# VGA_DAC.net
KiCad netlist of a schematic drawn in Altium Designer
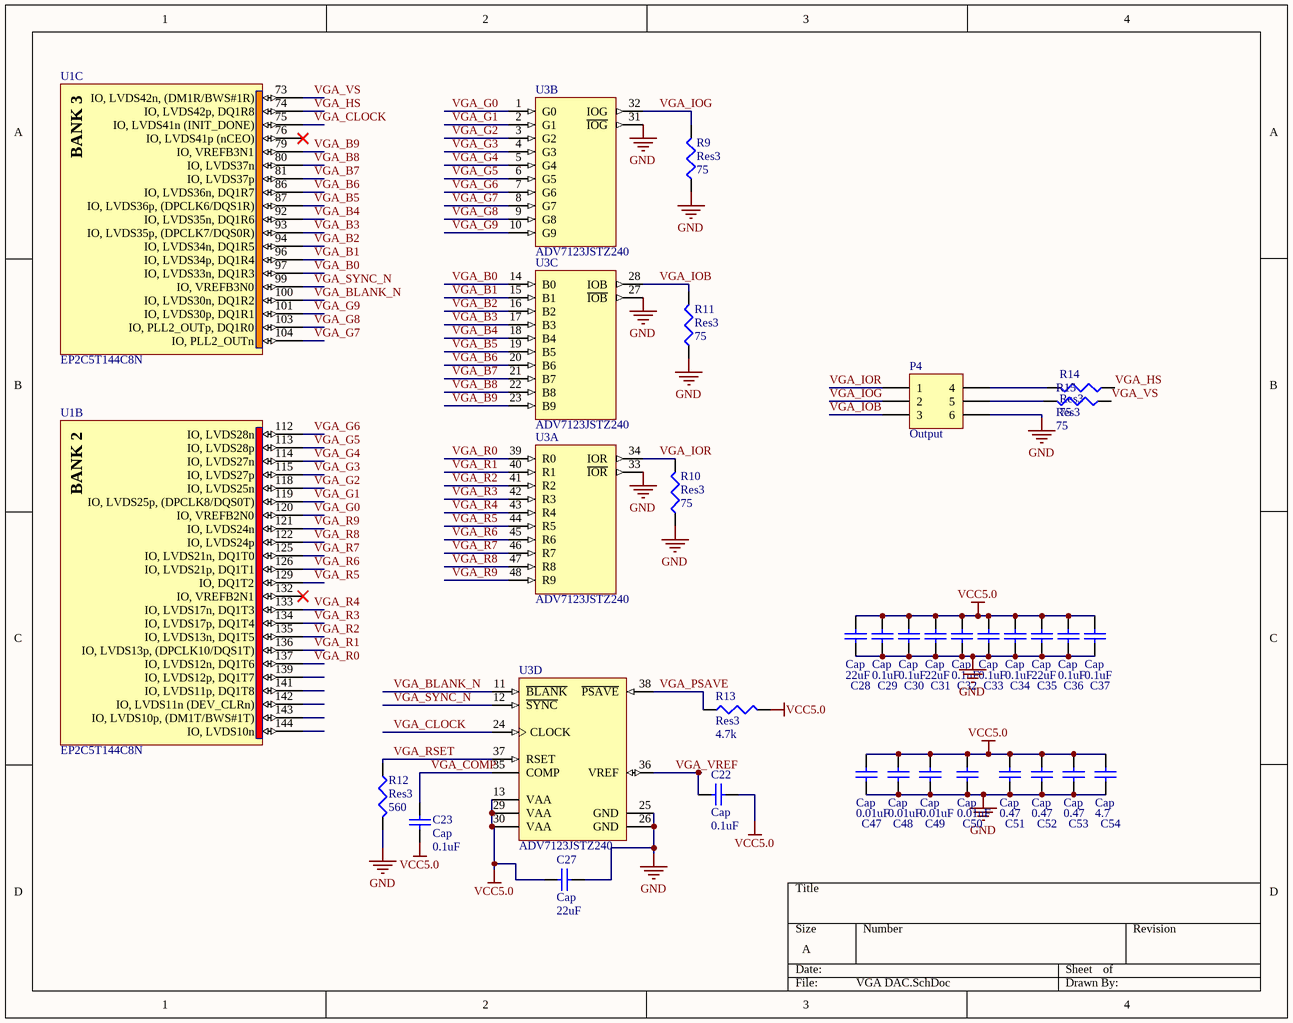
[diagram p0: VGA DAC.SchDoc]

(export (version "E")
  (design (tool "Eeschema 10.0.6"))
  (components
    (comp (ref "C22")
      (value "Cap")
      (footprint "1608[0603]")
      (description "Capacitor (Semiconductor SIM Model)")
      (fields (field (name "ALTIUM_VALUE") "0.1uF") (field (name "PUBLISHER") "Altium Limited"))
      (libsource (lib "Miscellaneous Devices") (part "Cap Semi"))
    )
    (comp (ref "C23")
      (value "Cap")
      (footprint "1608[0603]")
      (description "Capacitor (Semiconductor SIM Model)")
      (fields (field (name "ALTIUM_VALUE") "0.1uF") (field (name "PUBLISHER") "Altium Limited"))
      (libsource (lib "Miscellaneous Devices") (part "Cap Semi"))
    )
    (comp (ref "C27")
      (value "Cap")
      (footprint "1608[0603]")
      (description "Capacitor (Semiconductor SIM Model)")
      (fields (field (name "ALTIUM_VALUE") "22uF") (field (name "PUBLISHER") "Altium Limited"))
      (libsource (lib "Miscellaneous Devices") (part "Cap Semi"))
    )
    (comp (ref "C28")
      (value "Cap")
      (footprint "1608[0603]")
      (description "Capacitor (Semiconductor SIM Model)")
      (fields (field (name "ALTIUM_VALUE") "22uF") (field (name "PUBLISHER") "Altium Limited"))
      (libsource (lib "Miscellaneous Devices") (part "Cap Semi"))
    )
    (comp (ref "C29")
      (value "Cap")
      (footprint "1608[0603]")
      (description "Capacitor (Semiconductor SIM Model)")
      (fields (field (name "ALTIUM_VALUE") "0.1uF") (field (name "PUBLISHER") "Altium Limited"))
      (libsource (lib "Miscellaneous Devices") (part "Cap Semi"))
    )
    (comp (ref "C30")
      (value "Cap")
      (footprint "1608[0603]")
      (description "Capacitor (Semiconductor SIM Model)")
      (fields (field (name "ALTIUM_VALUE") "0.1uF") (field (name "PUBLISHER") "Altium Limited"))
      (libsource (lib "Miscellaneous Devices") (part "Cap Semi"))
    )
    (comp (ref "C31")
      (value "Cap")
      (footprint "1608[0603]")
      (description "Capacitor (Semiconductor SIM Model)")
      (fields (field (name "ALTIUM_VALUE") "22uF") (field (name "PUBLISHER") "Altium Limited"))
      (libsource (lib "Miscellaneous Devices") (part "Cap Semi"))
    )
    (comp (ref "C32")
      (value "Cap")
      (footprint "1608[0603]")
      (description "Capacitor (Semiconductor SIM Model)")
      (fields (field (name "ALTIUM_VALUE") "0.1uF") (field (name "PUBLISHER") "Altium Limited"))
      (libsource (lib "Miscellaneous Devices") (part "Cap Semi"))
    )
    (comp (ref "C33")
      (value "Cap")
      (footprint "1608[0603]")
      (description "Capacitor (Semiconductor SIM Model)")
      (fields (field (name "ALTIUM_VALUE") "0.1uF") (field (name "PUBLISHER") "Altium Limited"))
      (libsource (lib "Miscellaneous Devices") (part "Cap Semi"))
    )
    (comp (ref "C34")
      (value "Cap")
      (footprint "1608[0603]")
      (description "Capacitor (Semiconductor SIM Model)")
      (fields (field (name "ALTIUM_VALUE") "0.1uF") (field (name "PUBLISHER") "Altium Limited"))
      (libsource (lib "Miscellaneous Devices") (part "Cap Semi"))
    )
    (comp (ref "C35")
      (value "Cap")
      (footprint "1608[0603]")
      (description "Capacitor (Semiconductor SIM Model)")
      (fields (field (name "ALTIUM_VALUE") "22uF") (field (name "PUBLISHER") "Altium Limited"))
      (libsource (lib "Miscellaneous Devices") (part "Cap Semi"))
    )
    (comp (ref "C36")
      (value "Cap")
      (footprint "1608[0603]")
      (description "Capacitor (Semiconductor SIM Model)")
      (fields (field (name "ALTIUM_VALUE") "0.1uF") (field (name "PUBLISHER") "Altium Limited"))
      (libsource (lib "Miscellaneous Devices") (part "Cap Semi"))
    )
    (comp (ref "C37")
      (value "Cap")
      (footprint "1608[0603]")
      (description "Capacitor (Semiconductor SIM Model)")
      (fields (field (name "ALTIUM_VALUE") "0.1uF") (field (name "PUBLISHER") "Altium Limited"))
      (libsource (lib "Miscellaneous Devices") (part "Cap Semi"))
    )
    (comp (ref "C47")
      (value "Cap")
      (footprint "1608[0603]")
      (description "Capacitor (Semiconductor SIM Model)")
      (fields (field (name "ALTIUM_VALUE") "0.01uF") (field (name "PUBLISHER") "Altium Limited"))
      (libsource (lib "Miscellaneous Devices") (part "Cap Semi"))
    )
    (comp (ref "C48")
      (value "Cap")
      (footprint "1608[0603]")
      (description "Capacitor (Semiconductor SIM Model)")
      (fields (field (name "ALTIUM_VALUE") "0.01uF") (field (name "PUBLISHER") "Altium Limited"))
      (libsource (lib "Miscellaneous Devices") (part "Cap Semi"))
    )
    (comp (ref "C49")
      (value "Cap")
      (footprint "1608[0603]")
      (description "Capacitor (Semiconductor SIM Model)")
      (fields (field (name "ALTIUM_VALUE") "0.01uF") (field (name "PUBLISHER") "Altium Limited"))
      (libsource (lib "Miscellaneous Devices") (part "Cap Semi"))
    )
    (comp (ref "C50")
      (value "Cap")
      (footprint "1608[0603]")
      (description "Capacitor (Semiconductor SIM Model)")
      (fields (field (name "ALTIUM_VALUE") "0.01uF") (field (name "PUBLISHER") "Altium Limited"))
      (libsource (lib "Miscellaneous Devices") (part "Cap Semi"))
    )
    (comp (ref "C51")
      (value "Cap")
      (footprint "1608[0603]")
      (description "Capacitor (Semiconductor SIM Model)")
      (fields (field (name "ALTIUM_VALUE") "0.47") (field (name "PUBLISHER") "Altium Limited"))
      (libsource (lib "Miscellaneous Devices") (part "Cap Semi"))
    )
    (comp (ref "C52")
      (value "Cap")
      (footprint "1608[0603]")
      (description "Capacitor (Semiconductor SIM Model)")
      (fields (field (name "ALTIUM_VALUE") "0.47") (field (name "PUBLISHER") "Altium Limited"))
      (libsource (lib "Miscellaneous Devices") (part "Cap Semi"))
    )
    (comp (ref "C53")
      (value "Cap")
      (footprint "1608[0603]")
      (description "Capacitor (Semiconductor SIM Model)")
      (fields (field (name "ALTIUM_VALUE") "0.47") (field (name "PUBLISHER") "Altium Limited"))
      (libsource (lib "Miscellaneous Devices") (part "Cap Semi"))
    )
    (comp (ref "C54")
      (value "Cap")
      (footprint "1608[0603]")
      (description "Capacitor (Semiconductor SIM Model)")
      (fields (field (name "ALTIUM_VALUE") "4.7") (field (name "PUBLISHER") "Altium Limited"))
      (libsource (lib "Miscellaneous Devices") (part "Cap Semi"))
    )
    (comp (ref "P4")
      (value "Output")
      (footprint "HDR2X3_CEN")
      (description "Header, 3-Pin, Dual row")
      (fields (field (name "PUBLISHER") "Altium Limited"))
      (libsource (lib "Miscellaneous Connectors") (part "Header 3X2A"))
    )
    (comp (ref "R9")
      (value "Res3")
      (footprint "J1-0603")
      (description "Resistor")
      (fields (field (name "ALTIUM_VALUE") "75") (field (name "PUBLISHER") "Altium Limited"))
      (libsource (lib "Miscellaneous Devices") (part "Res3"))
    )
    (comp (ref "R10")
      (value "Res3")
      (footprint "J1-0603")
      (description "Resistor")
      (fields (field (name "ALTIUM_VALUE") "75") (field (name "PUBLISHER") "Altium Limited"))
      (libsource (lib "Miscellaneous Devices") (part "Res3"))
    )
    (comp (ref "R11")
      (value "Res3")
      (footprint "J1-0603")
      (description "Resistor")
      (fields (field (name "ALTIUM_VALUE") "75") (field (name "PUBLISHER") "Altium Limited"))
      (libsource (lib "Miscellaneous Devices") (part "Res3"))
    )
    (comp (ref "R12")
      (value "Res3")
      (footprint "J1-0603")
      (description "Resistor")
      (fields (field (name "ALTIUM_VALUE") "560") (field (name "PUBLISHER") "Altium Limited"))
      (libsource (lib "Miscellaneous Devices") (part "Res3"))
    )
    (comp (ref "R13")
      (value "Res3")
      (footprint "J1-0603")
      (description "Resistor")
      (fields (field (name "ALTIUM_VALUE") "4.7k") (field (name "PUBLISHER") "Altium Limited"))
      (libsource (lib "Miscellaneous Devices") (part "Res3"))
    )
    (comp (ref "R14")
      (value "Res3")
      (footprint "J1-0603")
      (description "Resistor")
      (fields (field (name "ALTIUM_VALUE") "75") (field (name "PUBLISHER") "Altium Limited"))
      (libsource (lib "Miscellaneous Devices") (part "Res3"))
    )
    (comp (ref "R15")
      (value "Res3")
      (footprint "J1-0603")
      (description "Resistor")
      (fields (field (name "ALTIUM_VALUE") "75") (field (name "PUBLISHER") "Altium Limited"))
      (libsource (lib "Miscellaneous Devices") (part "Res3"))
    )
    (comp (ref "U1")
      (value "EP2C5T144C8N")
      (footprint "TQFP144_N")
      (fields (field (name "PUBLISHER") "Altium Limited"))
      (libsource (lib "Altera Cyclone II") (part "EP2C5T144C8N"))
    )
    (comp (ref "U3")
      (value "ADV7123JSTZ240")
      (footprint "ST-48_N")
      (fields (field (name "GENERIC PART NUMBER") "ADV7123") (field (name "MANUFACTURER") "Analog Devices"))
      (libsource (lib "Analog Devices Data Converters Digital-to-Analog Converters") (part "ADV7123JSTZ240"))
    )
  )
  (nets
    (net (code "1") (name "/VGA_B0") (class "Default")
      (node (ref "U1") (pin "97") (pinfunction "IO,_LVDS33n,_DQ1R3_97") (pintype "bidirectional"))
      (node (ref "U3") (pin "14") (pinfunction "B0_14") (pintype "input"))
    )
    (net (code "2") (name "/VGA_B1") (class "Default")
      (node (ref "U1") (pin "96") (pinfunction "IO,_LVDS34p,_DQ1R4_96") (pintype "bidirectional"))
      (node (ref "U3") (pin "15") (pinfunction "B1_15") (pintype "input"))
    )
    (net (code "3") (name "/VGA_B2") (class "Default")
      (node (ref "U1") (pin "94") (pinfunction "IO,_LVDS34n,_DQ1R5_94") (pintype "bidirectional"))
      (node (ref "U3") (pin "16") (pinfunction "B2_16") (pintype "input"))
    )
    (net (code "4") (name "/VGA_B3") (class "Default")
      (node (ref "U1") (pin "93") (pinfunction "IO,_LVDS35p,_(DPCLK7/DQS0R)_93") (pintype "bidirectional"))
      (node (ref "U3") (pin "17") (pinfunction "B3_17") (pintype "input"))
    )
    (net (code "5") (name "/VGA_B4") (class "Default")
      (node (ref "U1") (pin "92") (pinfunction "IO,_LVDS35n,_DQ1R6_92") (pintype "bidirectional"))
      (node (ref "U3") (pin "18") (pinfunction "B4_18") (pintype "input"))
    )
    (net (code "6") (name "/VGA_B5") (class "Default")
      (node (ref "U1") (pin "87") (pinfunction "IO,_LVDS36p,_(DPCLK6/DQS1R)_87") (pintype "bidirectional"))
      (node (ref "U3") (pin "19") (pinfunction "B5_19") (pintype "input"))
    )
    (net (code "7") (name "/VGA_B6") (class "Default")
      (node (ref "U1") (pin "86") (pinfunction "IO,_LVDS36n,_DQ1R7_86") (pintype "bidirectional"))
      (node (ref "U3") (pin "20") (pinfunction "B6_20") (pintype "input"))
    )
    (net (code "8") (name "/VGA_B7") (class "Default")
      (node (ref "U1") (pin "81") (pinfunction "IO,_LVDS37p_81") (pintype "bidirectional"))
      (node (ref "U3") (pin "21") (pinfunction "B7_21") (pintype "input"))
    )
    (net (code "9") (name "/VGA_B8") (class "Default")
      (node (ref "U1") (pin "80") (pinfunction "IO,_LVDS37n_80") (pintype "bidirectional"))
      (node (ref "U3") (pin "22") (pinfunction "B8_22") (pintype "input"))
    )
    (net (code "10") (name "/VGA_B9") (class "Default")
      (node (ref "U1") (pin "79") (pinfunction "IO,_VREFB3N1_79") (pintype "bidirectional"))
      (node (ref "U3") (pin "23") (pinfunction "B9_23") (pintype "input"))
    )
    (net (code "11") (name "/VGA_BLANK_N") (class "Default")
      (node (ref "U1") (pin "100") (pinfunction "IO,_LVDS30n,_DQ1R2_100") (pintype "bidirectional"))
      (node (ref "U3") (pin "11") (pinfunction "~{BLANK}_11") (pintype "input"))
    )
    (net (code "12") (name "/VGA_CLOCK") (class "Default")
      (node (ref "U1") (pin "75") (pinfunction "IO,_LVDS41n_(INIT_DONE)_75") (pintype "bidirectional"))
      (node (ref "U3") (pin "24") (pinfunction "CLOCK_24") (pintype "input"))
    )
    (net (code "13") (name "/VGA_COMP") (class "Default")
      (node (ref "C23") (pin "1") (pinfunction "1_1") (pintype "passive"))
      (node (ref "U3") (pin "35") (pinfunction "COMP_35") (pintype "passive"))
    )
    (net (code "14") (name "/VGA_G0") (class "Default")
      (node (ref "U1") (pin "120") (pinfunction "IO,_VREFB2N0_120") (pintype "bidirectional"))
      (node (ref "U3") (pin "1") (pinfunction "G0_1") (pintype "input"))
    )
    (net (code "15") (name "/VGA_G1") (class "Default")
      (node (ref "U1") (pin "119") (pinfunction "IO,_LVDS25p,_(DPCLK8/DQS0T)_119") (pintype "bidirectional"))
      (node (ref "U3") (pin "2") (pinfunction "G1_2") (pintype "input"))
    )
    (net (code "16") (name "/VGA_G2") (class "Default")
      (node (ref "U1") (pin "118") (pinfunction "IO,_LVDS25n_118") (pintype "bidirectional"))
      (node (ref "U3") (pin "3") (pinfunction "G2_3") (pintype "input"))
    )
    (net (code "17") (name "/VGA_G3") (class "Default")
      (node (ref "U1") (pin "115") (pinfunction "IO,_LVDS27p_115") (pintype "bidirectional"))
      (node (ref "U3") (pin "4") (pinfunction "G3_4") (pintype "input"))
    )
    (net (code "18") (name "/VGA_G4") (class "Default")
      (node (ref "U1") (pin "114") (pinfunction "IO,_LVDS27n_114") (pintype "bidirectional"))
      (node (ref "U3") (pin "5") (pinfunction "G4_5") (pintype "input"))
    )
    (net (code "19") (name "/VGA_G5") (class "Default")
      (node (ref "U1") (pin "113") (pinfunction "IO,_LVDS28p_113") (pintype "bidirectional"))
      (node (ref "U3") (pin "6") (pinfunction "G5_6") (pintype "input"))
    )
    (net (code "20") (name "/VGA_G6") (class "Default")
      (node (ref "U1") (pin "112") (pinfunction "IO,_LVDS28n_112") (pintype "bidirectional"))
      (node (ref "U3") (pin "7") (pinfunction "G6_7") (pintype "input"))
    )
    (net (code "21") (name "/VGA_G7") (class "Default")
      (node (ref "U1") (pin "104") (pinfunction "IO,_PLL2_OUTn_104") (pintype "bidirectional"))
      (node (ref "U3") (pin "8") (pinfunction "G7_8") (pintype "input"))
    )
    (net (code "22") (name "/VGA_G8") (class "Default")
      (node (ref "U1") (pin "103") (pinfunction "IO,_PLL2_OUTp,_DQ1R0_103") (pintype "bidirectional"))
      (node (ref "U3") (pin "9") (pinfunction "G8_9") (pintype "input"))
    )
    (net (code "23") (name "/VGA_G9") (class "Default")
      (node (ref "U1") (pin "101") (pinfunction "IO,_LVDS30p,_DQ1R1_101") (pintype "bidirectional"))
      (node (ref "U3") (pin "10") (pinfunction "G9_10") (pintype "input"))
    )
    (net (code "24") (name "/VGA_HS") (class "Default")
      (node (ref "R14") (pin "1") (pinfunction "1_1") (pintype "passive"))
      (node (ref "U1") (pin "74") (pinfunction "IO,_LVDS42p,_DQ1R8_74") (pintype "bidirectional"))
    )
    (net (code "25") (name "/VGA_IOB") (class "Default")
      (node (ref "P4") (pin "3") (pinfunction "3_3") (pintype "passive"))
      (node (ref "R11") (pin "2") (pinfunction "2_2") (pintype "passive"))
      (node (ref "U3") (pin "28") (pinfunction "IOB_28") (pintype "output"))
    )
    (net (code "26") (name "/VGA_IOG") (class "Default")
      (node (ref "P4") (pin "2") (pinfunction "2_2") (pintype "passive"))
      (node (ref "R9") (pin "2") (pinfunction "2_2") (pintype "passive"))
      (node (ref "U3") (pin "32") (pinfunction "IOG_32") (pintype "output"))
    )
    (net (code "27") (name "/VGA_IOR") (class "Default")
      (node (ref "P4") (pin "1") (pinfunction "1_1") (pintype "passive"))
      (node (ref "R10") (pin "2") (pinfunction "2_2") (pintype "passive"))
      (node (ref "U3") (pin "34") (pinfunction "IOR_34") (pintype "output"))
    )
    (net (code "28") (name "/VGA_PSAVE") (class "Default")
      (node (ref "R13") (pin "1") (pinfunction "1_1") (pintype "passive"))
      (node (ref "U3") (pin "38") (pinfunction "~{PSAVE}_38") (pintype "input"))
    )
    (net (code "29") (name "/VGA_R0") (class "Default")
      (node (ref "U1") (pin "137") (pinfunction "IO,_LVDS12n,_DQ1T6_137") (pintype "bidirectional"))
      (node (ref "U3") (pin "39") (pinfunction "R0_39") (pintype "input"))
    )
    (net (code "30") (name "/VGA_R1") (class "Default")
      (node (ref "U1") (pin "136") (pinfunction "IO,_LVDS13p,_(DPCLK10/DQS1T)_136") (pintype "bidirectional"))
      (node (ref "U3") (pin "40") (pinfunction "R1_40") (pintype "input"))
    )
    (net (code "31") (name "/VGA_R2") (class "Default")
      (node (ref "U1") (pin "135") (pinfunction "IO,_LVDS13n,_DQ1T5_135") (pintype "bidirectional"))
      (node (ref "U3") (pin "41") (pinfunction "R2_41") (pintype "input"))
    )
    (net (code "32") (name "/VGA_R3") (class "Default")
      (node (ref "U1") (pin "134") (pinfunction "IO,_LVDS17p,_DQ1T4_134") (pintype "bidirectional"))
      (node (ref "U3") (pin "42") (pinfunction "R3_42") (pintype "input"))
    )
    (net (code "33") (name "/VGA_R4") (class "Default")
      (node (ref "U1") (pin "133") (pinfunction "IO,_LVDS17n,_DQ1T3_133") (pintype "bidirectional"))
      (node (ref "U3") (pin "43") (pinfunction "R4_43") (pintype "input"))
    )
    (net (code "34") (name "/VGA_R5") (class "Default")
      (node (ref "U1") (pin "129") (pinfunction "IO,_DQ1T2_129") (pintype "bidirectional"))
      (node (ref "U3") (pin "44") (pinfunction "R5_44") (pintype "input"))
    )
    (net (code "35") (name "/VGA_R6") (class "Default")
      (node (ref "U1") (pin "126") (pinfunction "IO,_LVDS21p,_DQ1T1_126") (pintype "bidirectional"))
      (node (ref "U3") (pin "45") (pinfunction "R6_45") (pintype "input"))
    )
    (net (code "36") (name "/VGA_R7") (class "Default")
      (node (ref "U1") (pin "125") (pinfunction "IO,_LVDS21n,_DQ1T0_125") (pintype "bidirectional"))
      (node (ref "U3") (pin "46") (pinfunction "R7_46") (pintype "input"))
    )
    (net (code "37") (name "/VGA_R8") (class "Default")
      (node (ref "U1") (pin "122") (pinfunction "IO,_LVDS24p_122") (pintype "bidirectional"))
      (node (ref "U3") (pin "47") (pinfunction "R8_47") (pintype "input"))
    )
    (net (code "38") (name "/VGA_R9") (class "Default")
      (node (ref "U1") (pin "121") (pinfunction "IO,_LVDS24n_121") (pintype "bidirectional"))
      (node (ref "U3") (pin "48") (pinfunction "R9_48") (pintype "input"))
    )
    (net (code "39") (name "/VGA_RSET") (class "Default")
      (node (ref "R12") (pin "1") (pinfunction "1_1") (pintype "passive"))
      (node (ref "U3") (pin "37") (pinfunction "RSET_37") (pintype "input"))
    )
    (net (code "40") (name "/VGA_SYNC_N") (class "Default")
      (node (ref "U1") (pin "99") (pinfunction "IO,_VREFB3N0_99") (pintype "bidirectional"))
      (node (ref "U3") (pin "12") (pinfunction "~{SYNC}_12") (pintype "input"))
    )
    (net (code "41") (name "/VGA_VREF") (class "Default")
      (node (ref "C22") (pin "2") (pinfunction "2_2") (pintype "passive"))
      (node (ref "U3") (pin "36") (pinfunction "VREF_36") (pintype "bidirectional"))
    )
    (net (code "42") (name "/VGA_VS") (class "Default")
      (node (ref "R15") (pin "1") (pinfunction "1_1") (pintype "passive"))
      (node (ref "U1") (pin "73") (pinfunction "IO,_LVDS42n,_(DM1R/BWS#1R)_73") (pintype "bidirectional"))
    )
    (net (code "43") (name "GND") (class "Default")
      (node (ref "C27") (pin "1") (pinfunction "1_1") (pintype "passive"))
      (node (ref "C28") (pin "2") (pinfunction "2_2") (pintype "passive"))
      (node (ref "C29") (pin "2") (pinfunction "2_2") (pintype "passive"))
      (node (ref "C30") (pin "2") (pinfunction "2_2") (pintype "passive"))
      (node (ref "C31") (pin "2") (pinfunction "2_2") (pintype "passive"))
      (node (ref "C32") (pin "2") (pinfunction "2_2") (pintype "passive"))
      (node (ref "C33") (pin "2") (pinfunction "2_2") (pintype "passive"))
      (node (ref "C34") (pin "2") (pinfunction "2_2") (pintype "passive"))
      (node (ref "C35") (pin "2") (pinfunction "2_2") (pintype "passive"))
      (node (ref "C36") (pin "2") (pinfunction "2_2") (pintype "passive"))
      (node (ref "C37") (pin "2") (pinfunction "2_2") (pintype "passive"))
      (node (ref "C47") (pin "2") (pinfunction "2_2") (pintype "passive"))
      (node (ref "C48") (pin "2") (pinfunction "2_2") (pintype "passive"))
      (node (ref "C49") (pin "2") (pinfunction "2_2") (pintype "passive"))
      (node (ref "C50") (pin "2") (pinfunction "2_2") (pintype "passive"))
      (node (ref "C51") (pin "2") (pinfunction "2_2") (pintype "passive"))
      (node (ref "C52") (pin "2") (pinfunction "2_2") (pintype "passive"))
      (node (ref "C53") (pin "2") (pinfunction "2_2") (pintype "passive"))
      (node (ref "C54") (pin "2") (pinfunction "2_2") (pintype "passive"))
      (node (ref "P4") (pin "6") (pinfunction "6_6") (pintype "passive"))
      (node (ref "R10") (pin "1") (pinfunction "1_1") (pintype "passive"))
      (node (ref "R11") (pin "1") (pinfunction "1_1") (pintype "passive"))
      (node (ref "R12") (pin "2") (pinfunction "2_2") (pintype "passive"))
      (node (ref "R9") (pin "1") (pinfunction "1_1") (pintype "passive"))
      (node (ref "U3") (pin "25") (pinfunction "GND_25") (pintype "power_in"))
      (node (ref "U3") (pin "26") (pinfunction "GND_26") (pintype "power_in"))
      (node (ref "U3") (pin "27") (pinfunction "~{IOB}_27") (pintype "output"))
      (node (ref "U3") (pin "31") (pinfunction "~{IOG}_31") (pintype "output"))
      (node (ref "U3") (pin "33") (pinfunction "~{IOR}_33") (pintype "output"))
    )
    (net (code "44") (name "Net-(P4-Pad4)") (class "Default")
      (node (ref "P4") (pin "4") (pinfunction "4_4") (pintype "passive"))
      (node (ref "R14") (pin "2") (pinfunction "2_2") (pintype "passive"))
    )
    (net (code "45") (name "Net-(P4-Pad5)") (class "Default")
      (node (ref "P4") (pin "5") (pinfunction "5_5") (pintype "passive"))
      (node (ref "R15") (pin "2") (pinfunction "2_2") (pintype "passive"))
    )
    (net (code "46") (name "VCC5.0") (class "Default")
      (node (ref "C22") (pin "1") (pinfunction "1_1") (pintype "passive"))
      (node (ref "C23") (pin "2") (pinfunction "2_2") (pintype "passive"))
      (node (ref "C27") (pin "2") (pinfunction "2_2") (pintype "passive"))
      (node (ref "C28") (pin "1") (pinfunction "1_1") (pintype "passive"))
      (node (ref "C29") (pin "1") (pinfunction "1_1") (pintype "passive"))
      (node (ref "C30") (pin "1") (pinfunction "1_1") (pintype "passive"))
      (node (ref "C31") (pin "1") (pinfunction "1_1") (pintype "passive"))
      (node (ref "C32") (pin "1") (pinfunction "1_1") (pintype "passive"))
      (node (ref "C33") (pin "1") (pinfunction "1_1") (pintype "passive"))
      (node (ref "C34") (pin "1") (pinfunction "1_1") (pintype "passive"))
      (node (ref "C35") (pin "1") (pinfunction "1_1") (pintype "passive"))
      (node (ref "C36") (pin "1") (pinfunction "1_1") (pintype "passive"))
      (node (ref "C37") (pin "1") (pinfunction "1_1") (pintype "passive"))
      (node (ref "C47") (pin "1") (pinfunction "1_1") (pintype "passive"))
      (node (ref "C48") (pin "1") (pinfunction "1_1") (pintype "passive"))
      (node (ref "C49") (pin "1") (pinfunction "1_1") (pintype "passive"))
      (node (ref "C50") (pin "1") (pinfunction "1_1") (pintype "passive"))
      (node (ref "C51") (pin "1") (pinfunction "1_1") (pintype "passive"))
      (node (ref "C52") (pin "1") (pinfunction "1_1") (pintype "passive"))
      (node (ref "C53") (pin "1") (pinfunction "1_1") (pintype "passive"))
      (node (ref "C54") (pin "1") (pinfunction "1_1") (pintype "passive"))
      (node (ref "R13") (pin "2") (pinfunction "2_2") (pintype "passive"))
      (node (ref "U3") (pin "13") (pinfunction "VAA_13") (pintype "power_in"))
      (node (ref "U3") (pin "29") (pinfunction "VAA_29") (pintype "power_in"))
      (node (ref "U3") (pin "30") (pinfunction "VAA_30") (pintype "power_in"))
    )
    (net (code "47") (name "unconnected-(U1B-IO,_LVDS10n-Pad144)") (class "Default")
      (node (ref "U1") (pin "144") (pinfunction "IO,_LVDS10n_144") (pintype "bidirectional"))
    )
    (net (code "48") (name "unconnected-(U1B-IO,_LVDS10p,_(DM1T{slash}BWS#1T)-Pad143)") (class "Default")
      (node (ref "U1") (pin "143") (pinfunction "IO,_LVDS10p,_(DM1T/BWS#1T)_143") (pintype "bidirectional"))
    )
    (net (code "49") (name "unconnected-(U1B-IO,_LVDS11n_(DEV_CLRn)-Pad142)") (class "Default")
      (node (ref "U1") (pin "142") (pinfunction "IO,_LVDS11n_(DEV_CLRn)_142") (pintype "bidirectional"))
    )
    (net (code "50") (name "unconnected-(U1B-IO,_LVDS11p,_DQ1T8-Pad141)") (class "Default")
      (node (ref "U1") (pin "141") (pinfunction "IO,_LVDS11p,_DQ1T8_141") (pintype "bidirectional"))
    )
    (net (code "51") (name "unconnected-(U1B-IO,_LVDS12p,_DQ1T7-Pad139)") (class "Default")
      (node (ref "U1") (pin "139") (pinfunction "IO,_LVDS12p,_DQ1T7_139") (pintype "bidirectional"))
    )
    (net (code "52") (name "unconnected-(U1B-IO,_VREFB2N1-Pad132)") (class "Default")
      (node (ref "U1") (pin "132") (pinfunction "IO,_VREFB2N1_132") (pintype "bidirectional+no_connect"))
    )
    (net (code "53") (name "unconnected-(U1C-IO,_LVDS41p_(nCEO)-Pad76)") (class "Default")
      (node (ref "U1") (pin "76") (pinfunction "IO,_LVDS41p_(nCEO)_76") (pintype "bidirectional+no_connect"))
    )
  )
)
